# NeoPI_W_v34.net
KiCad netlist of a schematic drawn in EAGLE
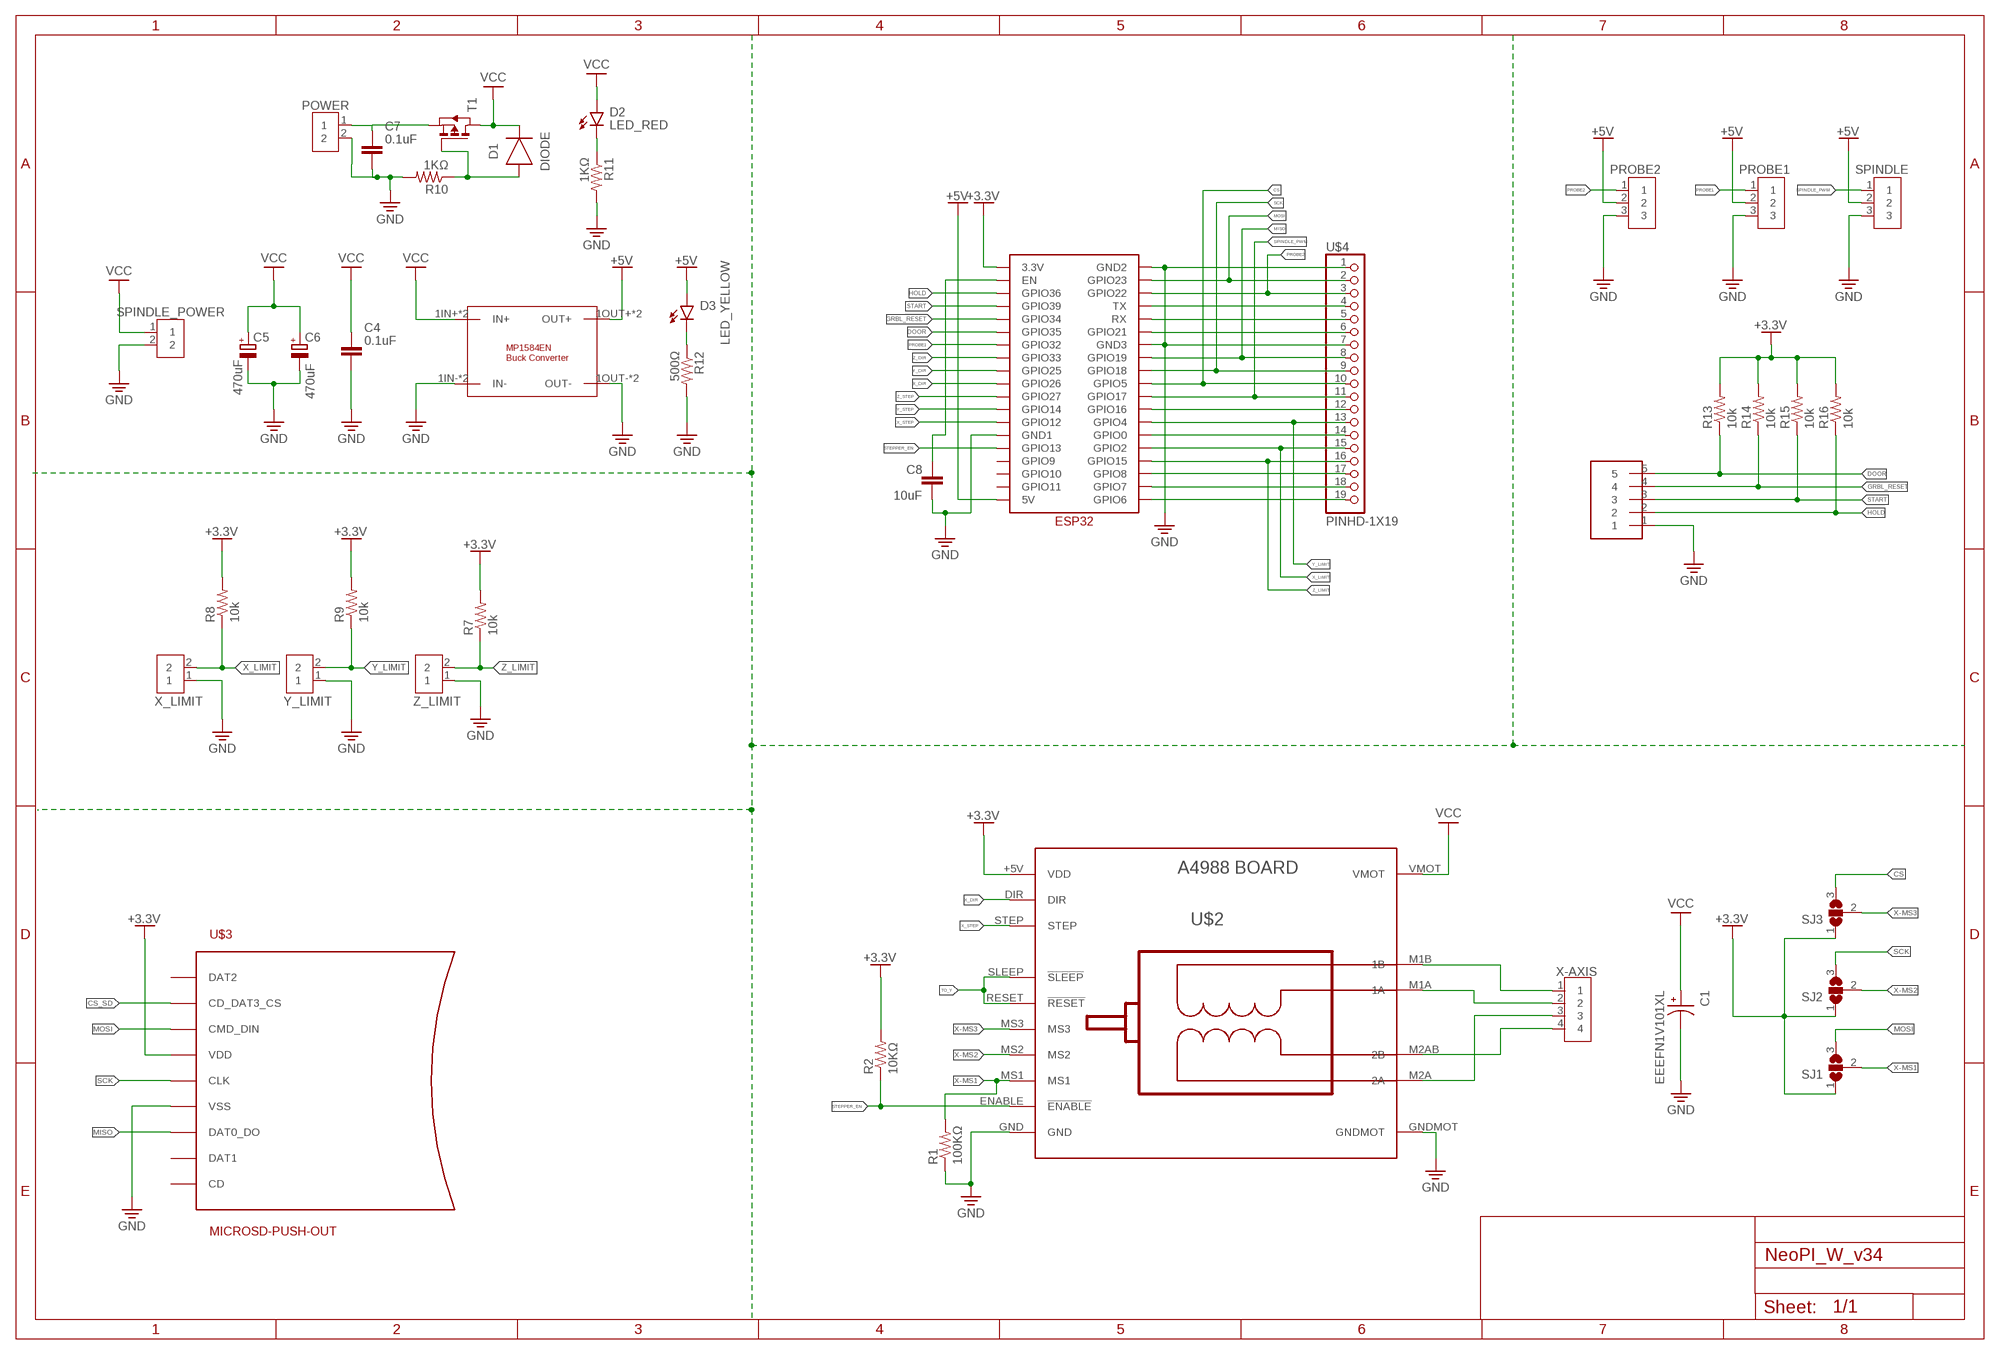
[diagram p0: schematic, sheet 1, part 1 of 2]
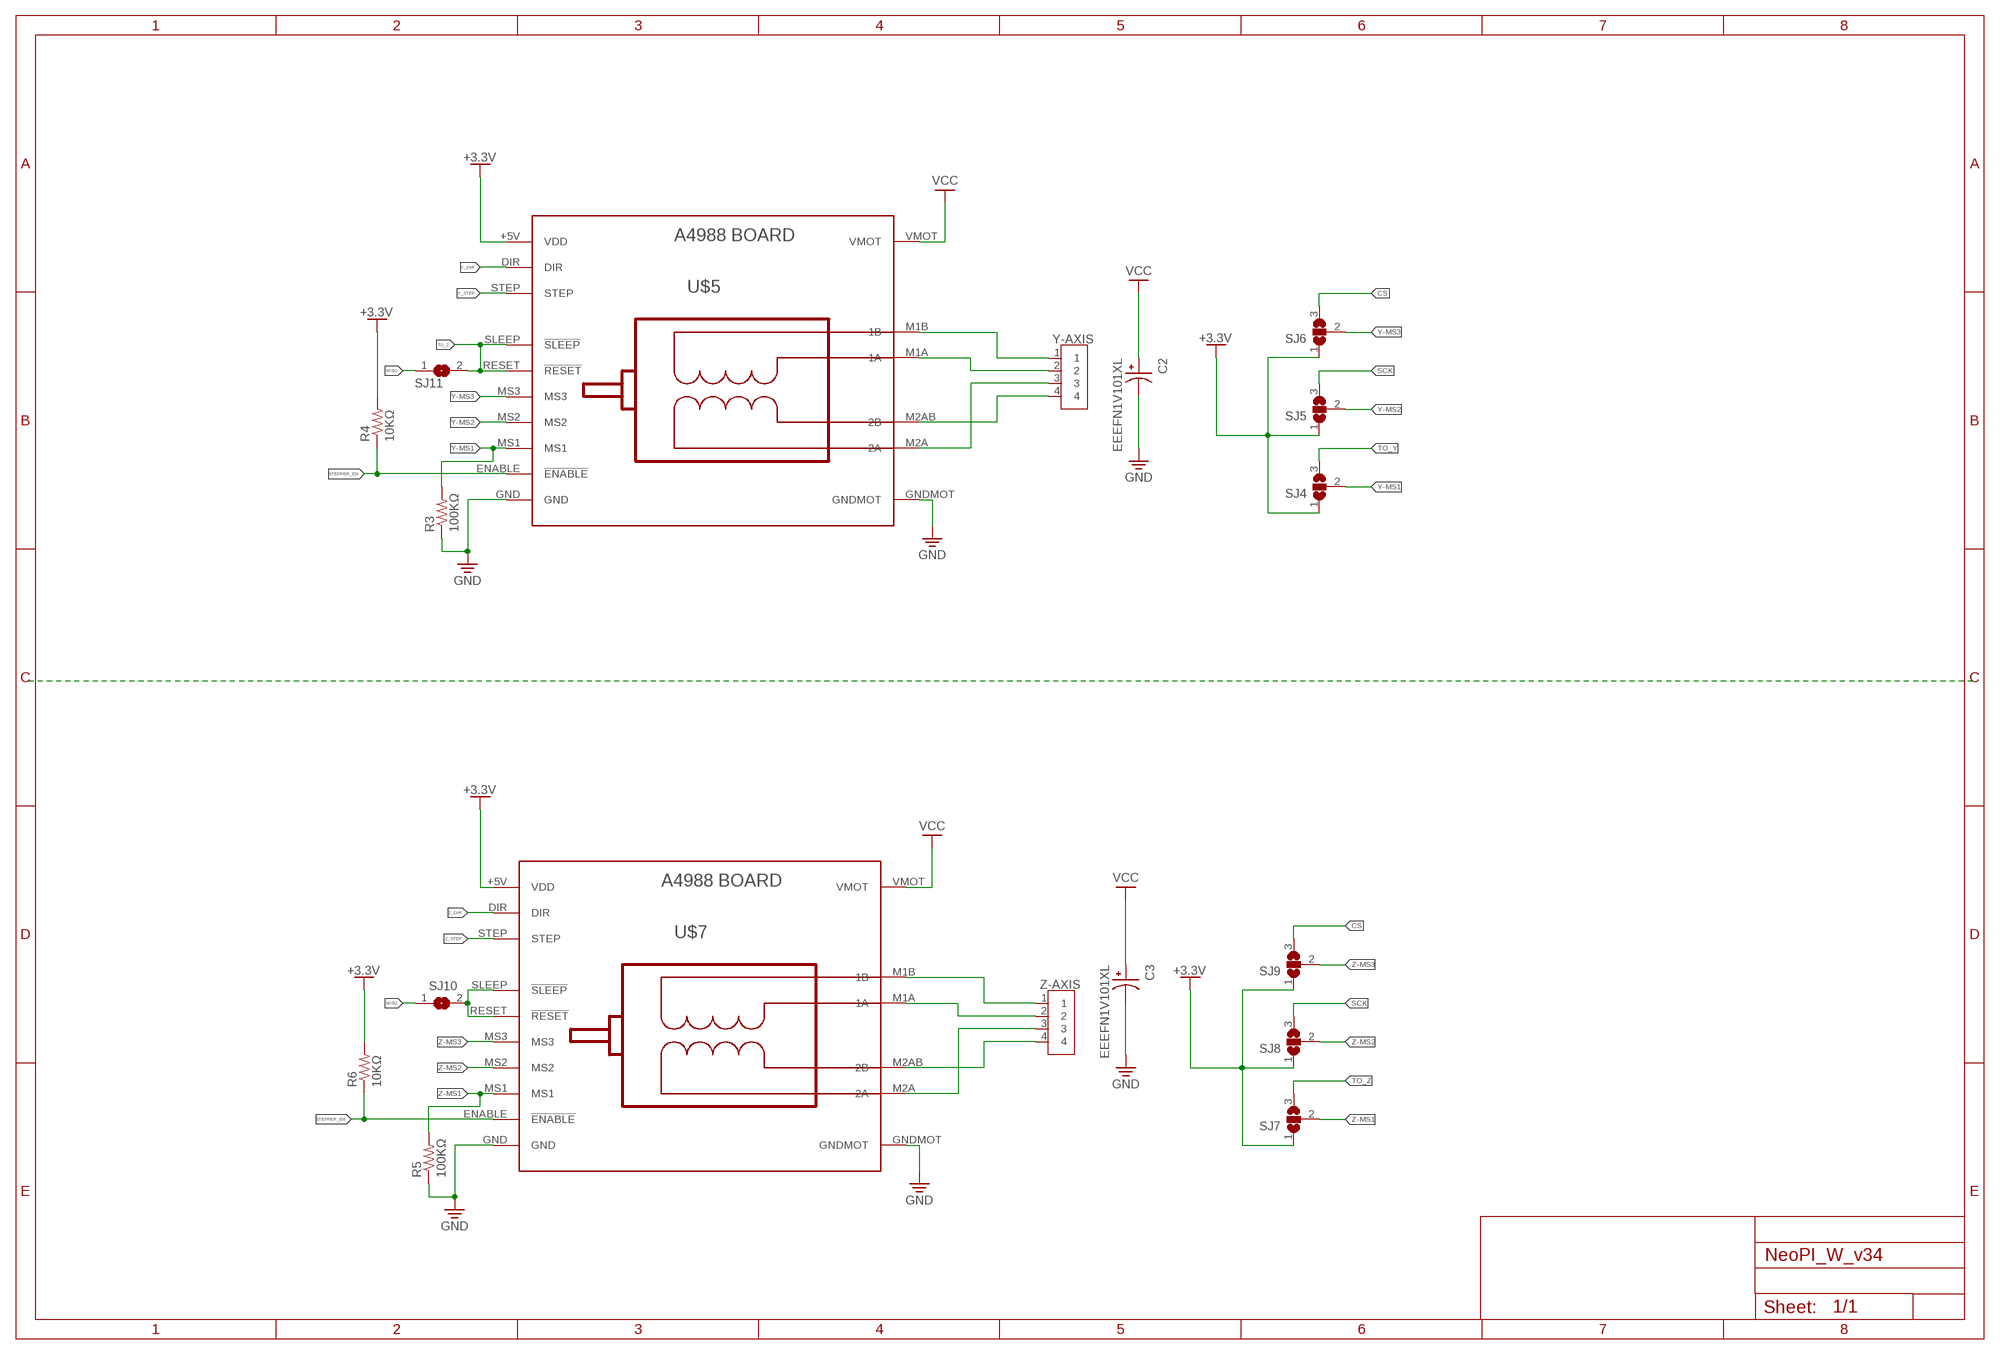
[diagram p1: schematic, sheet 1, part 2 of 2]

(export (version "E")
  (design (tool "Eeschema 10.0.6"))
  (components
    (comp (ref "C1")
      (value "EEEFN1V101XL")
      (footprint "eagle-import:CAP_EEEFN1V101XL")
      (fields (field (name "MANUFACTURER") "Panasonic"))
      (libsource (lib "eagle-import") (part "EEEFN1V101XL"))
    )
    (comp (ref "C2")
      (value "EEEFN1V101XL")
      (footprint "eagle-import:CAP_EEEFN1V101XL")
      (fields (field (name "MANUFACTURER") "Panasonic"))
      (libsource (lib "eagle-import") (part "EEEFN1V101XL"))
    )
    (comp (ref "C3")
      (value "EEEFN1V101XL")
      (footprint "eagle-import:CAP_EEEFN1V101XL")
      (fields (field (name "MANUFACTURER") "Panasonic"))
      (libsource (lib "eagle-import") (part "EEEFN1V101XL"))
    )
    (comp (ref "C4")
      (value "0.1uF")
      (footprint "eagle-import:CAPC3216X135")
      (libsource (lib "eagle-import") (part "CCHIP-1206(3216-METRIC)_"))
    )
    (comp (ref "C5")
      (value "470uF")
      (footprint "eagle-import:CAPAE1030X1050N")
      (libsource (lib "eagle-import") (part "C-POLECAP-10.5MM_"))
    )
    (comp (ref "C6")
      (value "470uF")
      (footprint "eagle-import:CAPAE1030X1050N")
      (libsource (lib "eagle-import") (part "C-POLECAP-10.5MM_"))
    )
    (comp (ref "C7")
      (value "0.1uF")
      (footprint "eagle-import:CAPC3216X135")
      (libsource (lib "eagle-import") (part "CCHIP-1206(3216-METRIC)_"))
    )
    (comp (ref "C8")
      (value "10uF")
      (footprint "eagle-import:CAPC3216X135")
      (libsource (lib "eagle-import") (part "CCHIP-1206(3216-METRIC)_"))
    )
    (comp (ref "D1")
      (value "DIODE")
      (footprint "eagle-import:DIOMELF5024")
      (libsource (lib "eagle-import") (part "DIODEDO-213AB(5025-METRIC)_"))
    )
    (comp (ref "D2")
      (value "LED_RED")
      (footprint "eagle-import:LEDC3216X75N_FLAT-R")
      (libsource (lib "eagle-import") (part "CHIP-FLAT-R_1206"))
    )
    (comp (ref "D3")
      (value "LED_YELLOW")
      (footprint "eagle-import:LEDC3216X75N_FLAT-Y")
      (libsource (lib "eagle-import") (part "CHIP-FLAT-Y_1206"))
    )
    (comp (ref "POWER")
      (value "2828XX-2282837-2")
      (footprint "eagle-import:TERMBLK_508-2N")
      (fields (field (name "MANUFACTURER") "TE Connectivity") (field (name "MPN") "282837-2"))
      (libsource (lib "eagle-import") (part "2828XX-2282837-2"))
    )
    (comp (ref "PROBE1")
      (value "2828XX-3282834-3")
      (footprint "eagle-import:TERMBLK_254-3N")
      (fields (field (name "MANUFACTURER") "TE Connectivity") (field (name "MPN") "282834-3"))
      (libsource (lib "eagle-import") (part "2828XX-3282834-3"))
    )
    (comp (ref "PROBE2")
      (value "2828XX-3282834-3")
      (footprint "eagle-import:TERMBLK_254-3N")
      (fields (field (name "MANUFACTURER") "TE Connectivity") (field (name "MPN") "282834-3"))
      (libsource (lib "eagle-import") (part "2828XX-3282834-3"))
    )
    (comp (ref "R1")
      (value "100KΩ")
      (footprint "eagle-import:R1206FAB")
      (libsource (lib "eagle-import") (part "RES-US1206FAB"))
    )
    (comp (ref "R2")
      (value "10KΩ")
      (footprint "eagle-import:R1206FAB")
      (libsource (lib "eagle-import") (part "RES-US1206FAB"))
    )
    (comp (ref "R3")
      (value "100KΩ")
      (footprint "eagle-import:R1206FAB")
      (libsource (lib "eagle-import") (part "RES-US1206FAB"))
    )
    (comp (ref "R4")
      (value "10KΩ")
      (footprint "eagle-import:R1206FAB")
      (libsource (lib "eagle-import") (part "RES-US1206FAB"))
    )
    (comp (ref "R5")
      (value "100KΩ")
      (footprint "eagle-import:R1206FAB")
      (libsource (lib "eagle-import") (part "RES-US1206FAB"))
    )
    (comp (ref "R6")
      (value "10KΩ")
      (footprint "eagle-import:R1206FAB")
      (libsource (lib "eagle-import") (part "RES-US1206FAB"))
    )
    (comp (ref "R7")
      (value "10k")
      (footprint "eagle-import:R1206FAB")
      (libsource (lib "eagle-import") (part "RES-US1206FAB"))
    )
    (comp (ref "R8")
      (value "10k")
      (footprint "eagle-import:R1206FAB")
      (libsource (lib "eagle-import") (part "RES-US1206FAB"))
    )
    (comp (ref "R9")
      (value "10k")
      (footprint "eagle-import:R1206FAB")
      (libsource (lib "eagle-import") (part "RES-US1206FAB"))
    )
    (comp (ref "R10")
      (value "1KΩ")
      (footprint "eagle-import:R1206FAB")
      (libsource (lib "eagle-import") (part "RES-US1206FAB"))
    )
    (comp (ref "R11")
      (value "1KΩ")
      (footprint "eagle-import:R1206FAB")
      (libsource (lib "eagle-import") (part "RES-US1206FAB"))
    )
    (comp (ref "R12")
      (value "500Ω")
      (footprint "eagle-import:R1206FAB")
      (libsource (lib "eagle-import") (part "RES-US1206FAB"))
    )
    (comp (ref "R13")
      (value "10k")
      (footprint "eagle-import:R1206FAB")
      (libsource (lib "eagle-import") (part "RES-US1206FAB"))
    )
    (comp (ref "R14")
      (value "10k")
      (footprint "eagle-import:R1206FAB")
      (libsource (lib "eagle-import") (part "RES-US1206FAB"))
    )
    (comp (ref "R15")
      (value "10k")
      (footprint "eagle-import:R1206FAB")
      (libsource (lib "eagle-import") (part "RES-US1206FAB"))
    )
    (comp (ref "R16")
      (value "10k")
      (footprint "eagle-import:R1206FAB")
      (libsource (lib "eagle-import") (part "RES-US1206FAB"))
    )
    (comp (ref "SJ1")
      (value "SJ2W")
      (footprint "eagle-import:SJ_2")
      (libsource (lib "eagle-import") (part "SJ2W"))
    )
    (comp (ref "SJ2")
      (value "SJ2W")
      (footprint "eagle-import:SJ_2")
      (libsource (lib "eagle-import") (part "SJ2W"))
    )
    (comp (ref "SJ3")
      (value "SJ2W")
      (footprint "eagle-import:SJ_2")
      (libsource (lib "eagle-import") (part "SJ2W"))
    )
    (comp (ref "SJ4")
      (value "SJ2W")
      (footprint "eagle-import:SJ_2")
      (libsource (lib "eagle-import") (part "SJ2W"))
    )
    (comp (ref "SJ5")
      (value "SJ2W")
      (footprint "eagle-import:SJ_2")
      (libsource (lib "eagle-import") (part "SJ2W"))
    )
    (comp (ref "SJ6")
      (value "SJ2W")
      (footprint "eagle-import:SJ_2")
      (libsource (lib "eagle-import") (part "SJ2W"))
    )
    (comp (ref "SJ7")
      (value "SJ2W")
      (footprint "eagle-import:SJ_2")
      (libsource (lib "eagle-import") (part "SJ2W"))
    )
    (comp (ref "SJ8")
      (value "SJ2W")
      (footprint "eagle-import:SJ_2")
      (libsource (lib "eagle-import") (part "SJ2W"))
    )
    (comp (ref "SJ9")
      (value "SJ2W")
      (footprint "eagle-import:SJ_2")
      (libsource (lib "eagle-import") (part "SJ2W"))
    )
    (comp (ref "SJ10")
      (value "SJ")
      (footprint "eagle-import:SJ")
      (libsource (lib "eagle-import") (part "SJ"))
    )
    (comp (ref "SJ11")
      (value "SJ")
      (footprint "eagle-import:SJ")
      (libsource (lib "eagle-import") (part "SJ"))
    )
    (comp (ref "SPINDLE")
      (value "2828XX-3282834-3")
      (footprint "eagle-import:TERMBLK_254-3N")
      (fields (field (name "MANUFACTURER") "TE Connectivity") (field (name "MPN") "282834-3"))
      (libsource (lib "eagle-import") (part "2828XX-3282834-3"))
    )
    (comp (ref "SPINDLE_POWER")
      (value "2828XX-2282837-2")
      (footprint "eagle-import:TERMBLK_508-2N")
      (fields (field (name "MANUFACTURER") "TE Connectivity") (field (name "MPN") "282837-2"))
      (libsource (lib "eagle-import") (part "2828XX-2282837-2"))
    )
    (comp (ref "T1")
      (value "PMOSFET")
      (footprint "eagle-import:TO252")
      (libsource (lib "eagle-import") (part "PMOSFET"))
    )
    (comp (ref "U$1")
      (value "ESP32_GRBL")
      (footprint "eagle-import:ESP32_GRBL")
      (libsource (lib "eagle-import") (part "ESP32_GRBL"))
    )
    (comp (ref "U$2")
      (value "BOARD_A4988")
      (footprint "eagle-import:BOARD_A4988")
      (libsource (lib "eagle-import") (part "BOARD_A4988"))
    )
    (comp (ref "U$3")
      (value "MICROSD-PUSH-OUT")
      (footprint "eagle-import:MICROSD-PUSH-OUT")
      (libsource (lib "eagle-import") (part "MICROSD-PUSH-OUT"))
    )
    (comp (ref "U$4")
      (value "PINHD-1X19")
      (footprint "eagle-import:1X19")
      (libsource (lib "eagle-import") (part "PINHD-1X19"))
    )
    (comp (ref "U$5")
      (value "BOARD_A4988")
      (footprint "eagle-import:BOARD_A4988")
      (libsource (lib "eagle-import") (part "BOARD_A4988"))
    )
    (comp (ref "U$6")
      (value "MINI-360_DC-TO-DC_BUCK_CONVERTER")
      (footprint "eagle-import:MINI_BUCK_CONVERTER")
      (libsource (lib "eagle-import") (part "MINI-360_DC-TO-DC_BUCK_CONVERTER"))
    )
    (comp (ref "U$7")
      (value "BOARD_A4988")
      (footprint "eagle-import:BOARD_A4988")
      (libsource (lib "eagle-import") (part "BOARD_A4988"))
    )
    (comp (ref "U$8")
      (value "1X05_SMD")
      (footprint "eagle-import:1X05_SMD")
      (libsource (lib "eagle-import") (part "1X05_SMD"))
    )
    (comp (ref "X-AXIS")
      (value "2828XX-4282837-4")
      (footprint "eagle-import:TERMBLK_508-4N")
      (fields (field (name "MANUFACTURER") "TE Connectivity") (field (name "MPN") "282837-4"))
      (libsource (lib "eagle-import") (part "2828XX-4282837-4"))
    )
    (comp (ref "X_LIMIT")
      (value "2828XX-2282834-2")
      (footprint "eagle-import:TERMBLK_254-2N")
      (libsource (lib "eagle-import") (part "2828XX-2282834-2"))
    )
    (comp (ref "Y-AXIS")
      (value "2828XX-4282837-4")
      (footprint "eagle-import:TERMBLK_508-4N")
      (fields (field (name "MANUFACTURER") "TE Connectivity") (field (name "MPN") "282837-4"))
      (libsource (lib "eagle-import") (part "2828XX-4282837-4"))
    )
    (comp (ref "Y_LIMIT")
      (value "2828XX-2282834-2")
      (footprint "eagle-import:TERMBLK_254-2N")
      (libsource (lib "eagle-import") (part "2828XX-2282834-2"))
    )
    (comp (ref "Z-AXIS")
      (value "2828XX-4282837-4")
      (footprint "eagle-import:TERMBLK_508-4N")
      (fields (field (name "MANUFACTURER") "TE Connectivity") (field (name "MPN") "282837-4"))
      (libsource (lib "eagle-import") (part "2828XX-4282837-4"))
    )
    (comp (ref "Z_LIMIT")
      (value "2828XX-2282834-2")
      (footprint "eagle-import:TERMBLK_254-2N")
      (libsource (lib "eagle-import") (part "2828XX-2282834-2"))
    )
  )
  (nets
    (net (code "1") (name "+3.3V") (class "Default")
      (node (ref "R13") (pin "2") (pinfunction "2_2") (pintype "passive"))
      (node (ref "R14") (pin "2") (pinfunction "2_2") (pintype "passive"))
      (node (ref "R15") (pin "2") (pinfunction "2_2") (pintype "passive"))
      (node (ref "R16") (pin "2") (pinfunction "2_2") (pintype "passive"))
      (node (ref "R2") (pin "2") (pinfunction "2_2") (pintype "passive"))
      (node (ref "R4") (pin "2") (pinfunction "2_2") (pintype "passive"))
      (node (ref "R6") (pin "2") (pinfunction "2_2") (pintype "passive"))
      (node (ref "R7") (pin "2") (pinfunction "2_2") (pintype "passive"))
      (node (ref "R8") (pin "2") (pinfunction "2_2") (pintype "passive"))
      (node (ref "R9") (pin "2") (pinfunction "2_2") (pintype "passive"))
      (node (ref "SJ1") (pin "1") (pinfunction "1_1") (pintype "passive"))
      (node (ref "SJ2") (pin "1") (pinfunction "1_1") (pintype "passive"))
      (node (ref "SJ3") (pin "1") (pinfunction "1_1") (pintype "passive"))
      (node (ref "SJ4") (pin "1") (pinfunction "1_1") (pintype "passive"))
      (node (ref "SJ5") (pin "1") (pinfunction "1_1") (pintype "passive"))
      (node (ref "SJ6") (pin "1") (pinfunction "1_1") (pintype "passive"))
      (node (ref "SJ7") (pin "1") (pinfunction "1_1") (pintype "passive"))
      (node (ref "SJ8") (pin "1") (pinfunction "1_1") (pintype "passive"))
      (node (ref "SJ9") (pin "1") (pinfunction "1_1") (pintype "passive"))
      (node (ref "U$1") (pin "3.3V") (pinfunction "3.3V_3.3V") (pintype "bidirectional"))
      (node (ref "U$2") (pin "+5V") (pinfunction "VDD_+5V") (pintype "power_in"))
      (node (ref "U$3") (pin "4") (pinfunction "VDD_4") (pintype "bidirectional"))
      (node (ref "U$5") (pin "+5V") (pinfunction "VDD_+5V") (pintype "power_in"))
      (node (ref "U$7") (pin "+5V") (pinfunction "VDD_+5V") (pintype "power_in"))
    )
    (net (code "2") (name "+5V") (class "Default")
      (node (ref "D3") (pin "A") (pinfunction "A_A") (pintype "passive"))
      (node (ref "PROBE1") (pin "2") (pinfunction "2_2") (pintype "bidirectional"))
      (node (ref "PROBE2") (pin "2") (pinfunction "2_2") (pintype "bidirectional"))
      (node (ref "SPINDLE") (pin "2") (pinfunction "2_2") (pintype "bidirectional"))
      (node (ref "U$1") (pin "5V") (pinfunction "5V_5V") (pintype "bidirectional"))
      (node (ref "U$6") (pin "1OUT+") (pinfunction "OUT+_1OUT+") (pintype "bidirectional"))
      (node (ref "U$6") (pin "2OUT+") (pinfunction "OUT+_2OUT+") (pintype "bidirectional"))
    )
    (net (code "3") (name "CS") (class "Default")
      (node (ref "SJ3") (pin "3") (pinfunction "3_3") (pintype "passive"))
      (node (ref "SJ6") (pin "3") (pinfunction "3_3") (pintype "passive"))
      (node (ref "SJ9") (pin "3") (pinfunction "3_3") (pintype "passive"))
      (node (ref "U$1") (pin "GPIO5") (pinfunction "GPIO5_GPIO5") (pintype "bidirectional"))
      (node (ref "U$4") (pin "10") (pinfunction "10_10") (pintype "passive"))
    )
    (net (code "4") (name "CS_SD") (class "Default")
      (node (ref "U$3") (pin "2") (pinfunction "CD_DAT3_CS_2") (pintype "bidirectional"))
    )
    (net (code "5") (name "DOOR") (class "Default")
      (node (ref "R13") (pin "1") (pinfunction "1_1") (pintype "passive"))
      (node (ref "U$1") (pin "GPIO35") (pinfunction "GPIO35_GPIO35") (pintype "bidirectional"))
      (node (ref "U$8") (pin "5") (pinfunction "5_5") (pintype "bidirectional"))
    )
    (net (code "6") (name "GND") (class "Default")
      (node (ref "C1") (pin "2") (pinfunction "2_2") (pintype "passive"))
      (node (ref "C2") (pin "2") (pinfunction "2_2") (pintype "passive"))
      (node (ref "C3") (pin "2") (pinfunction "2_2") (pintype "passive"))
      (node (ref "C4") (pin "2") (pinfunction "2_2") (pintype "passive"))
      (node (ref "C5") (pin "2") (pinfunction "-_2") (pintype "passive"))
      (node (ref "C6") (pin "2") (pinfunction "-_2") (pintype "passive"))
      (node (ref "C7") (pin "2") (pinfunction "2_2") (pintype "passive"))
      (node (ref "C8") (pin "2") (pinfunction "2_2") (pintype "passive"))
      (node (ref "POWER") (pin "2") (pinfunction "2_2") (pintype "bidirectional"))
      (node (ref "PROBE1") (pin "3") (pinfunction "3_3") (pintype "bidirectional"))
      (node (ref "PROBE2") (pin "3") (pinfunction "3_3") (pintype "bidirectional"))
      (node (ref "R1") (pin "1") (pinfunction "1_1") (pintype "passive"))
      (node (ref "R10") (pin "2") (pinfunction "2_2") (pintype "passive"))
      (node (ref "R11") (pin "2") (pinfunction "2_2") (pintype "passive"))
      (node (ref "R12") (pin "2") (pinfunction "2_2") (pintype "passive"))
      (node (ref "R3") (pin "1") (pinfunction "1_1") (pintype "passive"))
      (node (ref "R5") (pin "1") (pinfunction "1_1") (pintype "passive"))
      (node (ref "SPINDLE") (pin "3") (pinfunction "3_3") (pintype "bidirectional"))
      (node (ref "SPINDLE_POWER") (pin "2") (pinfunction "2_2") (pintype "bidirectional"))
      (node (ref "U$1") (pin "GND1") (pinfunction "GND1_GND1") (pintype "bidirectional"))
      (node (ref "U$1") (pin "GND2") (pinfunction "GND2_GND2") (pintype "bidirectional"))
      (node (ref "U$1") (pin "GND3") (pinfunction "GND3_GND3") (pintype "bidirectional"))
      (node (ref "U$2") (pin "GND") (pinfunction "GND_GND") (pintype "power_in"))
      (node (ref "U$2") (pin "GNDMOT") (pinfunction "GNDMOT_GNDMOT") (pintype "power_in"))
      (node (ref "U$3") (pin "6") (pinfunction "VSS_6") (pintype "bidirectional"))
      (node (ref "U$3") (pin "G1") (pinfunction "VSS_G1") (pintype "bidirectional"))
      (node (ref "U$3") (pin "G2") (pinfunction "VSS_G2") (pintype "bidirectional"))
      (node (ref "U$3") (pin "G3") (pinfunction "VSS_G3") (pintype "bidirectional"))
      (node (ref "U$3") (pin "G4") (pinfunction "VSS_G4") (pintype "bidirectional"))
      (node (ref "U$4") (pin "1") (pinfunction "1_1") (pintype "passive"))
      (node (ref "U$4") (pin "7") (pinfunction "7_7") (pintype "passive"))
      (node (ref "U$5") (pin "GND") (pinfunction "GND_GND") (pintype "power_in"))
      (node (ref "U$5") (pin "GNDMOT") (pinfunction "GNDMOT_GNDMOT") (pintype "power_in"))
      (node (ref "U$6") (pin "1IN-") (pinfunction "IN-_1IN-") (pintype "bidirectional"))
      (node (ref "U$6") (pin "1OUT-") (pinfunction "OUT-_1OUT-") (pintype "bidirectional"))
      (node (ref "U$6") (pin "2IN-") (pinfunction "IN-_2IN-") (pintype "bidirectional"))
      (node (ref "U$6") (pin "2OUT-") (pinfunction "OUT-_2OUT-") (pintype "bidirectional"))
      (node (ref "U$7") (pin "GND") (pinfunction "GND_GND") (pintype "power_in"))
      (node (ref "U$7") (pin "GNDMOT") (pinfunction "GNDMOT_GNDMOT") (pintype "power_in"))
      (node (ref "U$8") (pin "1") (pinfunction "1_1") (pintype "bidirectional"))
      (node (ref "X_LIMIT") (pin "1") (pinfunction "1_1") (pintype "bidirectional"))
      (node (ref "Y_LIMIT") (pin "1") (pinfunction "1_1") (pintype "bidirectional"))
      (node (ref "Z_LIMIT") (pin "1") (pinfunction "1_1") (pintype "bidirectional"))
    )
    (net (code "7") (name "GRBL_RESET") (class "Default")
      (node (ref "R14") (pin "1") (pinfunction "1_1") (pintype "passive"))
      (node (ref "U$1") (pin "GPIO34") (pinfunction "GPIO34_GPIO34") (pintype "bidirectional"))
      (node (ref "U$8") (pin "4") (pinfunction "4_4") (pintype "bidirectional"))
    )
    (net (code "8") (name "HOLD") (class "Default")
      (node (ref "R16") (pin "1") (pinfunction "1_1") (pintype "passive"))
      (node (ref "U$1") (pin "GPIO36") (pinfunction "GPIO36_GPIO36") (pintype "bidirectional"))
      (node (ref "U$8") (pin "2") (pinfunction "2_2") (pintype "bidirectional"))
    )
    (net (code "9") (name "MISO") (class "Default")
      (node (ref "SJ10") (pin "1") (pinfunction "1_1") (pintype "passive"))
      (node (ref "SJ11") (pin "1") (pinfunction "1_1") (pintype "passive"))
      (node (ref "U$1") (pin "GPIO19") (pinfunction "GPIO19_GPIO19") (pintype "bidirectional"))
      (node (ref "U$3") (pin "7") (pinfunction "DAT0_DO_7") (pintype "bidirectional"))
      (node (ref "U$4") (pin "8") (pinfunction "8_8") (pintype "passive"))
    )
    (net (code "10") (name "MOSI") (class "Default")
      (node (ref "SJ1") (pin "3") (pinfunction "3_3") (pintype "passive"))
      (node (ref "U$1") (pin "GPIO23") (pinfunction "GPIO23_GPIO23") (pintype "bidirectional"))
      (node (ref "U$3") (pin "3") (pinfunction "CMD_DIN_3") (pintype "bidirectional"))
      (node (ref "U$4") (pin "2") (pinfunction "2_2") (pintype "passive"))
    )
    (net (code "11") (name "Net-(C8-Pad1)") (class "Default")
      (node (ref "C8") (pin "1") (pinfunction "1_1") (pintype "passive"))
      (node (ref "U$1") (pin "EN") (pinfunction "EN_EN") (pintype "bidirectional"))
    )
    (net (code "12") (name "Net-(D1-A)") (class "Default")
      (node (ref "D1") (pin "2") (pinfunction "A_2") (pintype "passive"))
      (node (ref "R10") (pin "1") (pinfunction "1_1") (pintype "passive"))
      (node (ref "T1") (pin "1") (pinfunction "G_1") (pintype "passive"))
    )
    (net (code "13") (name "Net-(D2-PadC)") (class "Default")
      (node (ref "D2") (pin "C") (pinfunction "C_C") (pintype "passive"))
      (node (ref "R11") (pin "1") (pinfunction "1_1") (pintype "passive"))
    )
    (net (code "14") (name "Net-(D3-PadC)") (class "Default")
      (node (ref "D3") (pin "C") (pinfunction "C_C") (pintype "passive"))
      (node (ref "R12") (pin "1") (pinfunction "1_1") (pintype "passive"))
    )
    (net (code "15") (name "Net-(T1-S)") (class "Default")
      (node (ref "C7") (pin "1") (pinfunction "1_1") (pintype "passive"))
      (node (ref "POWER") (pin "1") (pinfunction "1_1") (pintype "bidirectional"))
      (node (ref "T1") (pin "2") (pinfunction "S_2") (pintype "passive"))
    )
    (net (code "16") (name "Net-(U$1-PadGPIO0)") (class "Default")
      (node (ref "U$1") (pin "GPIO0") (pinfunction "GPIO0_GPIO0") (pintype "bidirectional"))
      (node (ref "U$4") (pin "14") (pinfunction "14_14") (pintype "passive"))
    )
    (net (code "17") (name "Net-(U$1-PadGPIO6)") (class "Default")
      (node (ref "U$1") (pin "GPIO6") (pinfunction "GPIO6_GPIO6") (pintype "bidirectional"))
      (node (ref "U$4") (pin "19") (pinfunction "19_19") (pintype "passive"))
    )
    (net (code "18") (name "Net-(U$1-PadGPIO7)") (class "Default")
      (node (ref "U$1") (pin "GPIO7") (pinfunction "GPIO7_GPIO7") (pintype "bidirectional"))
      (node (ref "U$4") (pin "18") (pinfunction "18_18") (pintype "passive"))
    )
    (net (code "19") (name "Net-(U$1-PadGPIO8)") (class "Default")
      (node (ref "U$1") (pin "GPIO8") (pinfunction "GPIO8_GPIO8") (pintype "bidirectional"))
      (node (ref "U$4") (pin "17") (pinfunction "17_17") (pintype "passive"))
    )
    (net (code "20") (name "Net-(U$1-PadGPIO16)") (class "Default")
      (node (ref "U$1") (pin "GPIO16") (pinfunction "GPIO16_GPIO16") (pintype "bidirectional"))
      (node (ref "U$4") (pin "12") (pinfunction "12_12") (pintype "passive"))
    )
    (net (code "21") (name "Net-(U$1-PadGPIO21)") (class "Default")
      (node (ref "U$1") (pin "GPIO21") (pinfunction "GPIO21_GPIO21") (pintype "bidirectional"))
      (node (ref "U$4") (pin "6") (pinfunction "6_6") (pintype "passive"))
    )
    (net (code "22") (name "Net-(U$1-PadRX)") (class "Default")
      (node (ref "U$1") (pin "RX") (pinfunction "RX_RX") (pintype "bidirectional"))
      (node (ref "U$4") (pin "5") (pinfunction "5_5") (pintype "passive"))
    )
    (net (code "23") (name "Net-(U$1-PadTX)") (class "Default")
      (node (ref "U$1") (pin "TX") (pinfunction "TX_TX") (pintype "bidirectional"))
      (node (ref "U$4") (pin "4") (pinfunction "4_4") (pintype "passive"))
    )
    (net (code "24") (name "Net-(U$2-1A)") (class "Default")
      (node (ref "U$2") (pin "M1A") (pinfunction "1A_M1A") (pintype "output"))
      (node (ref "X-AXIS") (pin "2") (pinfunction "2_2") (pintype "bidirectional"))
    )
    (net (code "25") (name "Net-(U$2-1B)") (class "Default")
      (node (ref "U$2") (pin "M1B") (pinfunction "1B_M1B") (pintype "output"))
      (node (ref "X-AXIS") (pin "1") (pinfunction "1_1") (pintype "bidirectional"))
    )
    (net (code "26") (name "Net-(U$2-2A)") (class "Default")
      (node (ref "U$2") (pin "M2A") (pinfunction "2A_M2A") (pintype "output"))
      (node (ref "X-AXIS") (pin "3") (pinfunction "3_3") (pintype "bidirectional"))
    )
    (net (code "27") (name "Net-(U$2-2B)") (class "Default")
      (node (ref "U$2") (pin "M2AB") (pinfunction "2B_M2AB") (pintype "output"))
      (node (ref "X-AXIS") (pin "4") (pinfunction "4_4") (pintype "bidirectional"))
    )
    (net (code "28") (name "Net-(U$5-1A)") (class "Default")
      (node (ref "U$5") (pin "M1A") (pinfunction "1A_M1A") (pintype "output"))
      (node (ref "Y-AXIS") (pin "2") (pinfunction "2_2") (pintype "bidirectional"))
    )
    (net (code "29") (name "Net-(U$5-1B)") (class "Default")
      (node (ref "U$5") (pin "M1B") (pinfunction "1B_M1B") (pintype "output"))
      (node (ref "Y-AXIS") (pin "1") (pinfunction "1_1") (pintype "bidirectional"))
    )
    (net (code "30") (name "Net-(U$5-2A)") (class "Default")
      (node (ref "U$5") (pin "M2A") (pinfunction "2A_M2A") (pintype "output"))
      (node (ref "Y-AXIS") (pin "3") (pinfunction "3_3") (pintype "bidirectional"))
    )
    (net (code "31") (name "Net-(U$5-2B)") (class "Default")
      (node (ref "U$5") (pin "M2AB") (pinfunction "2B_M2AB") (pintype "output"))
      (node (ref "Y-AXIS") (pin "4") (pinfunction "4_4") (pintype "bidirectional"))
    )
    (net (code "32") (name "Net-(U$7-1A)") (class "Default")
      (node (ref "U$7") (pin "M1A") (pinfunction "1A_M1A") (pintype "output"))
      (node (ref "Z-AXIS") (pin "2") (pinfunction "2_2") (pintype "bidirectional"))
    )
    (net (code "33") (name "Net-(U$7-1B)") (class "Default")
      (node (ref "U$7") (pin "M1B") (pinfunction "1B_M1B") (pintype "output"))
      (node (ref "Z-AXIS") (pin "1") (pinfunction "1_1") (pintype "bidirectional"))
    )
    (net (code "34") (name "Net-(U$7-2A)") (class "Default")
      (node (ref "U$7") (pin "M2A") (pinfunction "2A_M2A") (pintype "output"))
      (node (ref "Z-AXIS") (pin "3") (pinfunction "3_3") (pintype "bidirectional"))
    )
    (net (code "35") (name "Net-(U$7-2B)") (class "Default")
      (node (ref "U$7") (pin "M2AB") (pinfunction "2B_M2AB") (pintype "output"))
      (node (ref "Z-AXIS") (pin "4") (pinfunction "4_4") (pintype "bidirectional"))
    )
    (net (code "36") (name "Net-(U$7-~{RESET})") (class "Default")
      (node (ref "SJ10") (pin "2") (pinfunction "2_2") (pintype "passive"))
      (node (ref "U$7") (pin "RESET") (pinfunction "~{RESET}_RESET") (pintype "input"))
      (node (ref "U$7") (pin "SLEEP") (pinfunction "~{SLEEP}_SLEEP") (pintype "input"))
    )
    (net (code "37") (name "PROBE1") (class "Default")
      (node (ref "PROBE1") (pin "1") (pinfunction "1_1") (pintype "bidirectional"))
      (node (ref "U$1") (pin "GPIO32") (pinfunction "GPIO32_GPIO32") (pintype "bidirectional"))
    )
    (net (code "38") (name "PROBE2") (class "Default")
      (node (ref "PROBE2") (pin "1") (pinfunction "1_1") (pintype "bidirectional"))
      (node (ref "U$1") (pin "GPIO22") (pinfunction "GPIO22_GPIO22") (pintype "bidirectional"))
      (node (ref "U$4") (pin "3") (pinfunction "3_3") (pintype "passive"))
    )
    (net (code "39") (name "SCK") (class "Default")
      (node (ref "SJ2") (pin "3") (pinfunction "3_3") (pintype "passive"))
      (node (ref "SJ5") (pin "3") (pinfunction "3_3") (pintype "passive"))
      (node (ref "SJ8") (pin "3") (pinfunction "3_3") (pintype "passive"))
      (node (ref "U$1") (pin "GPIO18") (pinfunction "GPIO18_GPIO18") (pintype "bidirectional"))
      (node (ref "U$3") (pin "5") (pinfunction "CLK_5") (pintype "bidirectional"))
      (node (ref "U$4") (pin "9") (pinfunction "9_9") (pintype "passive"))
    )
    (net (code "40") (name "SPINDLE_PWM") (class "Default")
      (node (ref "SPINDLE") (pin "1") (pinfunction "1_1") (pintype "bidirectional"))
      (node (ref "U$1") (pin "GPIO17") (pinfunction "GPIO17_GPIO17") (pintype "bidirectional"))
      (node (ref "U$4") (pin "11") (pinfunction "11_11") (pintype "passive"))
    )
    (net (code "41") (name "START") (class "Default")
      (node (ref "R15") (pin "1") (pinfunction "1_1") (pintype "passive"))
      (node (ref "U$1") (pin "GPIO39") (pinfunction "GPIO39_GPIO39") (pintype "bidirectional"))
      (node (ref "U$8") (pin "3") (pinfunction "3_3") (pintype "bidirectional"))
    )
    (net (code "42") (name "STEPPER_EN") (class "Default")
      (node (ref "R2") (pin "1") (pinfunction "1_1") (pintype "passive"))
      (node (ref "R4") (pin "1") (pinfunction "1_1") (pintype "passive"))
      (node (ref "R6") (pin "1") (pinfunction "1_1") (pintype "passive"))
      (node (ref "U$1") (pin "GPIO13") (pinfunction "GPIO13_GPIO13") (pintype "bidirectional"))
      (node (ref "U$2") (pin "ENABLE") (pinfunction "~{ENABLE}_ENABLE") (pintype "input"))
      (node (ref "U$5") (pin "ENABLE") (pinfunction "~{ENABLE}_ENABLE") (pintype "input"))
      (node (ref "U$7") (pin "ENABLE") (pinfunction "~{ENABLE}_ENABLE") (pintype "input"))
    )
    (net (code "43") (name "TO_Y") (class "Default")
      (node (ref "SJ4") (pin "3") (pinfunction "3_3") (pintype "passive"))
      (node (ref "U$2") (pin "RESET") (pinfunction "~{RESET}_RESET") (pintype "input"))
      (node (ref "U$2") (pin "SLEEP") (pinfunction "~{SLEEP}_SLEEP") (pintype "input"))
    )
    (net (code "44") (name "TO_Z") (class "Default")
      (node (ref "SJ11") (pin "2") (pinfunction "2_2") (pintype "passive"))
      (node (ref "SJ7") (pin "3") (pinfunction "3_3") (pintype "passive"))
      (node (ref "U$5") (pin "RESET") (pinfunction "~{RESET}_RESET") (pintype "input"))
      (node (ref "U$5") (pin "SLEEP") (pinfunction "~{SLEEP}_SLEEP") (pintype "input"))
    )
    (net (code "45") (name "VCC") (class "Default")
      (node (ref "C1") (pin "1") (pinfunction "1_1") (pintype "passive"))
      (node (ref "C2") (pin "1") (pinfunction "1_1") (pintype "passive"))
      (node (ref "C3") (pin "1") (pinfunction "1_1") (pintype "passive"))
      (node (ref "C4") (pin "1") (pinfunction "1_1") (pintype "passive"))
      (node (ref "C5") (pin "1") (pinfunction "+_1") (pintype "passive"))
      (node (ref "C6") (pin "1") (pinfunction "+_1") (pintype "passive"))
      (node (ref "D1") (pin "1") (pinfunction "C_1") (pintype "passive"))
      (node (ref "D2") (pin "A") (pinfunction "A_A") (pintype "passive"))
      (node (ref "SPINDLE_POWER") (pin "1") (pinfunction "1_1") (pintype "bidirectional"))
      (node (ref "T1") (pin "3") (pinfunction "D_3") (pintype "passive"))
      (node (ref "U$2") (pin "VMOT") (pinfunction "VMOT_VMOT") (pintype "power_in"))
      (node (ref "U$5") (pin "VMOT") (pinfunction "VMOT_VMOT") (pintype "power_in"))
      (node (ref "U$6") (pin "1IN+") (pinfunction "IN+_1IN+") (pintype "bidirectional"))
      (node (ref "U$6") (pin "2IN+") (pinfunction "IN+_2IN+") (pintype "bidirectional"))
      (node (ref "U$7") (pin "VMOT") (pinfunction "VMOT_VMOT") (pintype "power_in"))
    )
    (net (code "46") (name "X-MS1") (class "Default")
      (node (ref "R1") (pin "2") (pinfunction "2_2") (pintype "passive"))
      (node (ref "SJ1") (pin "2") (pinfunction "2_2") (pintype "passive"))
      (node (ref "U$2") (pin "MS1") (pinfunction "MS1_MS1") (pintype "input"))
    )
    (net (code "47") (name "X-MS2") (class "Default")
      (node (ref "SJ2") (pin "2") (pinfunction "2_2") (pintype "passive"))
      (node (ref "U$2") (pin "MS2") (pinfunction "MS2_MS2") (pintype "input"))
    )
    (net (code "48") (name "X-MS3") (class "Default")
      (node (ref "SJ3") (pin "2") (pinfunction "2_2") (pintype "passive"))
      (node (ref "U$2") (pin "MS3") (pinfunction "MS3_MS3") (pintype "input"))
    )
    (net (code "49") (name "X_DIR") (class "Default")
      (node (ref "U$1") (pin "GPIO26") (pinfunction "GPIO26_GPIO26") (pintype "bidirectional"))
      (node (ref "U$2") (pin "DIR") (pinfunction "DIR_DIR") (pintype "input"))
    )
    (net (code "50") (name "X_LIMIT") (class "Default")
      (node (ref "R8") (pin "1") (pinfunction "1_1") (pintype "passive"))
      (node (ref "U$1") (pin "GPIO2") (pinfunction "GPIO2_GPIO2") (pintype "bidirectional"))
      (node (ref "U$4") (pin "15") (pinfunction "15_15") (pintype "passive"))
      (node (ref "X_LIMIT") (pin "2") (pinfunction "2_2") (pintype "bidirectional"))
    )
    (net (code "51") (name "X_STEP") (class "Default")
      (node (ref "U$1") (pin "GPIO12") (pinfunction "GPIO12_GPIO12") (pintype "bidirectional"))
      (node (ref "U$2") (pin "STEP") (pinfunction "STEP_STEP") (pintype "input"))
    )
    (net (code "52") (name "Y-MS1") (class "Default")
      (node (ref "R3") (pin "2") (pinfunction "2_2") (pintype "passive"))
      (node (ref "SJ4") (pin "2") (pinfunction "2_2") (pintype "passive"))
      (node (ref "U$5") (pin "MS1") (pinfunction "MS1_MS1") (pintype "input"))
    )
    (net (code "53") (name "Y-MS2") (class "Default")
      (node (ref "SJ5") (pin "2") (pinfunction "2_2") (pintype "passive"))
      (node (ref "U$5") (pin "MS2") (pinfunction "MS2_MS2") (pintype "input"))
    )
    (net (code "54") (name "Y-MS3") (class "Default")
      (node (ref "SJ6") (pin "2") (pinfunction "2_2") (pintype "passive"))
      (node (ref "U$5") (pin "MS3") (pinfunction "MS3_MS3") (pintype "input"))
    )
    (net (code "55") (name "Y_DIR") (class "Default")
      (node (ref "U$1") (pin "GPIO25") (pinfunction "GPIO25_GPIO25") (pintype "bidirectional"))
      (node (ref "U$5") (pin "DIR") (pinfunction "DIR_DIR") (pintype "input"))
    )
    (net (code "56") (name "Y_LIMIT") (class "Default")
      (node (ref "R9") (pin "1") (pinfunction "1_1") (pintype "passive"))
      (node (ref "U$1") (pin "GPIO4") (pinfunction "GPIO4_GPIO4") (pintype "bidirectional"))
      (node (ref "U$4") (pin "13") (pinfunction "13_13") (pintype "passive"))
      (node (ref "Y_LIMIT") (pin "2") (pinfunction "2_2") (pintype "bidirectional"))
    )
    (net (code "57") (name "Y_STEP") (class "Default")
      (node (ref "U$1") (pin "GPIO14") (pinfunction "GPIO14_GPIO14") (pintype "bidirectional"))
      (node (ref "U$5") (pin "STEP") (pinfunction "STEP_STEP") (pintype "input"))
    )
    (net (code "58") (name "Z-MS1") (class "Default")
      (node (ref "R5") (pin "2") (pinfunction "2_2") (pintype "passive"))
      (node (ref "SJ7") (pin "2") (pinfunction "2_2") (pintype "passive"))
      (node (ref "U$7") (pin "MS1") (pinfunction "MS1_MS1") (pintype "input"))
    )
    (net (code "59") (name "Z-MS2") (class "Default")
      (node (ref "SJ8") (pin "2") (pinfunction "2_2") (pintype "passive"))
      (node (ref "U$7") (pin "MS2") (pinfunction "MS2_MS2") (pintype "input"))
    )
    (net (code "60") (name "Z-MS3") (class "Default")
      (node (ref "SJ9") (pin "2") (pinfunction "2_2") (pintype "passive"))
      (node (ref "U$7") (pin "MS3") (pinfunction "MS3_MS3") (pintype "input"))
    )
    (net (code "61") (name "Z_DIR") (class "Default")
      (node (ref "U$1") (pin "GPIO33") (pinfunction "GPIO33_GPIO33") (pintype "bidirectional"))
      (node (ref "U$7") (pin "DIR") (pinfunction "DIR_DIR") (pintype "input"))
    )
    (net (code "62") (name "Z_LIMIT") (class "Default")
      (node (ref "R7") (pin "1") (pinfunction "1_1") (pintype "passive"))
      (node (ref "U$1") (pin "GPIO15") (pinfunction "GPIO15_GPIO15") (pintype "bidirectional"))
      (node (ref "U$4") (pin "16") (pinfunction "16_16") (pintype "passive"))
      (node (ref "Z_LIMIT") (pin "2") (pinfunction "2_2") (pintype "bidirectional"))
    )
    (net (code "63") (name "Z_STEP") (class "Default")
      (node (ref "U$1") (pin "GPIO27") (pinfunction "GPIO27_GPIO27") (pintype "bidirectional"))
      (node (ref "U$7") (pin "STEP") (pinfunction "STEP_STEP") (pintype "input"))
    )
    (net (code "64") (name "unconnected-(U$1-PadGPIO9)") (class "Default")
      (node (ref "U$1") (pin "GPIO9") (pinfunction "GPIO9_GPIO9") (pintype "bidirectional"))
    )
    (net (code "65") (name "unconnected-(U$1-PadGPIO10)") (class "Default")
      (node (ref "U$1") (pin "GPIO10") (pinfunction "GPIO10_GPIO10") (pintype "bidirectional"))
    )
    (net (code "66") (name "unconnected-(U$1-PadGPIO11)") (class "Default")
      (node (ref "U$1") (pin "GPIO11") (pinfunction "GPIO11_GPIO11") (pintype "bidirectional"))
    )
    (net (code "67") (name "unconnected-(U$3-DAT1-Pad8)") (class "Default")
      (node (ref "U$3") (pin "8") (pinfunction "DAT1_8") (pintype "bidirectional"))
    )
    (net (code "68") (name "unconnected-(U$3-DAT2-Pad1)") (class "Default")
      (node (ref "U$3") (pin "1") (pinfunction "DAT2_1") (pintype "bidirectional"))
    )
    (net (code "69") (name "unconnected-(U$3-PadCD)") (class "Default")
      (node (ref "U$3") (pin "CD") (pinfunction "CD_CD") (pintype "bidirectional"))
    )
  )
)
